# 2364_ROM-el_v2.net
KiCad netlist of a schematic drawn in EAGLE
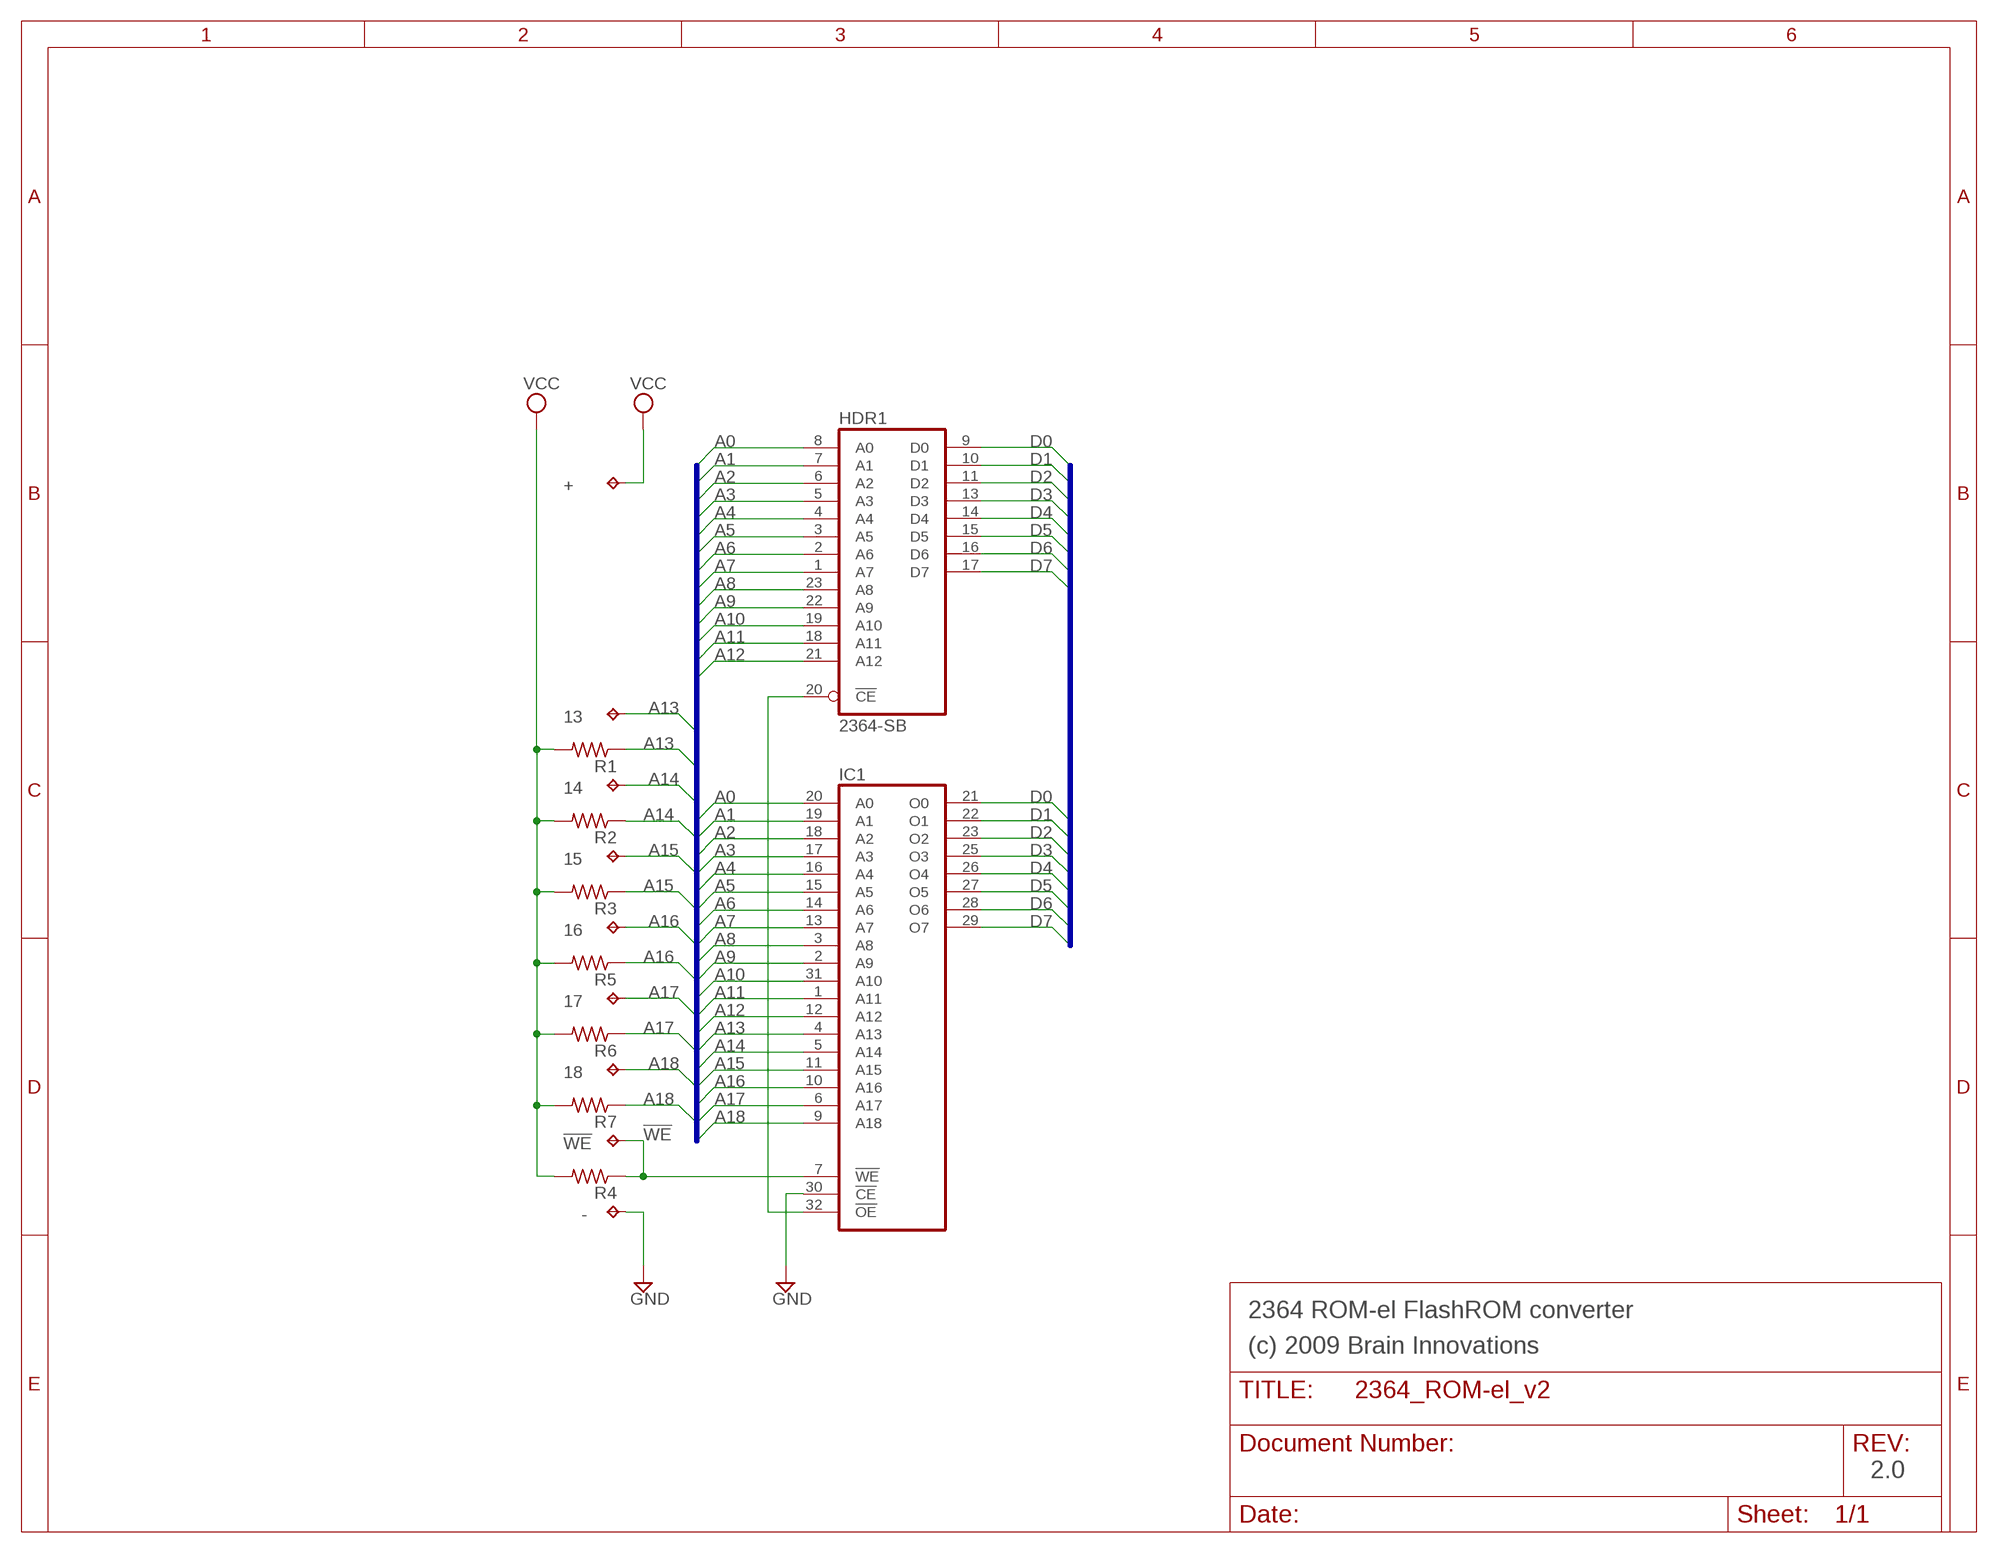
[diagram p0: schematic, sheet 1]

(export (version "E")
  (design (tool "Eeschema 10.0.6"))
  (components
    (comp (ref "!WE")
      (value "TPTP13SQ")
      (footprint "eagle-import:TP13SQ")
      (libsource (lib "eagle-import") (part "TPTP13SQ"))
    )
    (comp (ref "+")
      (value "TPTP13SQ")
      (footprint "eagle-import:TP13SQ")
      (libsource (lib "eagle-import") (part "TPTP13SQ"))
    )
    (comp (ref "-")
      (value "TPTP13SQ")
      (footprint "eagle-import:TP13SQ")
      (libsource (lib "eagle-import") (part "TPTP13SQ"))
    )
    (comp (ref "13")
      (value "TPTP13SQ")
      (footprint "eagle-import:TP13SQ")
      (libsource (lib "eagle-import") (part "TPTP13SQ"))
    )
    (comp (ref "14")
      (value "TPTP13SQ")
      (footprint "eagle-import:TP13SQ")
      (libsource (lib "eagle-import") (part "TPTP13SQ"))
    )
    (comp (ref "15")
      (value "TPTP13SQ")
      (footprint "eagle-import:TP13SQ")
      (libsource (lib "eagle-import") (part "TPTP13SQ"))
    )
    (comp (ref "16")
      (value "TPTP13SQ")
      (footprint "eagle-import:TP13SQ")
      (libsource (lib "eagle-import") (part "TPTP13SQ"))
    )
    (comp (ref "17")
      (value "TPTP13SQ")
      (footprint "eagle-import:TP13SQ")
      (libsource (lib "eagle-import") (part "TPTP13SQ"))
    )
    (comp (ref "18")
      (value "TPTP13SQ")
      (footprint "eagle-import:TP13SQ")
      (libsource (lib "eagle-import") (part "TPTP13SQ"))
    )
    (comp (ref "HDR1")
      (value "2364-SB")
      (footprint "eagle-import:DIL24-SMD-REVERSE")
      (libsource (lib "eagle-import") (part "2364-SB"))
    )
    (comp (ref "IC1")
      (value "FLASH_RAM4096KB'V'")
      (footprint "eagle-import:VSOP32")
      (libsource (lib "eagle-import") (part "FLASH_RAM4096KB'V'"))
    )
    (comp (ref "R1")
      (value "R-US_R0402")
      (footprint "eagle-import:R0402")
      (libsource (lib "eagle-import") (part "R-US_R0402"))
    )
    (comp (ref "R2")
      (value "R-US_R0402")
      (footprint "eagle-import:R0402")
      (libsource (lib "eagle-import") (part "R-US_R0402"))
    )
    (comp (ref "R3")
      (value "R-US_R0402")
      (footprint "eagle-import:R0402")
      (libsource (lib "eagle-import") (part "R-US_R0402"))
    )
    (comp (ref "R4")
      (value "R-US_R0402")
      (footprint "eagle-import:R0402")
      (libsource (lib "eagle-import") (part "R-US_R0402"))
    )
    (comp (ref "R5")
      (value "R-US_R0402")
      (footprint "eagle-import:R0402")
      (libsource (lib "eagle-import") (part "R-US_R0402"))
    )
    (comp (ref "R6")
      (value "R-US_R0402")
      (footprint "eagle-import:R0402")
      (libsource (lib "eagle-import") (part "R-US_R0402"))
    )
    (comp (ref "R7")
      (value "R-US_R0402")
      (footprint "eagle-import:R0402")
      (libsource (lib "eagle-import") (part "R-US_R0402"))
    )
  )
  (nets
    (net (code "1") (name "/A0") (class "Default")
      (node (ref "HDR1") (pin "8") (pinfunction "A0_8") (pintype "bidirectional"))
      (node (ref "IC1") (pin "20") (pinfunction "A0_20") (pintype "input"))
    )
    (net (code "2") (name "/A1") (class "Default")
      (node (ref "HDR1") (pin "7") (pinfunction "A1_7") (pintype "bidirectional"))
      (node (ref "IC1") (pin "19") (pinfunction "A1_19") (pintype "input"))
    )
    (net (code "3") (name "/A2") (class "Default")
      (node (ref "HDR1") (pin "6") (pinfunction "A2_6") (pintype "bidirectional"))
      (node (ref "IC1") (pin "18") (pinfunction "A2_18") (pintype "input"))
    )
    (net (code "4") (name "/A3") (class "Default")
      (node (ref "HDR1") (pin "5") (pinfunction "A3_5") (pintype "bidirectional"))
      (node (ref "IC1") (pin "17") (pinfunction "A3_17") (pintype "input"))
    )
    (net (code "5") (name "/A4") (class "Default")
      (node (ref "HDR1") (pin "4") (pinfunction "A4_4") (pintype "bidirectional"))
      (node (ref "IC1") (pin "16") (pinfunction "A4_16") (pintype "input"))
    )
    (net (code "6") (name "/A5") (class "Default")
      (node (ref "HDR1") (pin "3") (pinfunction "A5_3") (pintype "bidirectional"))
      (node (ref "IC1") (pin "15") (pinfunction "A5_15") (pintype "input"))
    )
    (net (code "7") (name "/A6") (class "Default")
      (node (ref "HDR1") (pin "2") (pinfunction "A6_2") (pintype "bidirectional"))
      (node (ref "IC1") (pin "14") (pinfunction "A6_14") (pintype "input"))
    )
    (net (code "8") (name "/A7") (class "Default")
      (node (ref "HDR1") (pin "1") (pinfunction "A7_1") (pintype "bidirectional"))
      (node (ref "IC1") (pin "13") (pinfunction "A7_13") (pintype "input"))
    )
    (net (code "9") (name "/A8") (class "Default")
      (node (ref "HDR1") (pin "23") (pinfunction "A8_23") (pintype "bidirectional"))
      (node (ref "IC1") (pin "3") (pinfunction "A8_3") (pintype "input"))
    )
    (net (code "10") (name "/A9") (class "Default")
      (node (ref "HDR1") (pin "22") (pinfunction "A9_22") (pintype "bidirectional"))
      (node (ref "IC1") (pin "2") (pinfunction "A9_2") (pintype "input"))
    )
    (net (code "11") (name "/A10") (class "Default")
      (node (ref "HDR1") (pin "19") (pinfunction "A10_19") (pintype "bidirectional"))
      (node (ref "IC1") (pin "31") (pinfunction "A10_31") (pintype "input"))
    )
    (net (code "12") (name "/A11") (class "Default")
      (node (ref "HDR1") (pin "18") (pinfunction "A11_18") (pintype "bidirectional"))
      (node (ref "IC1") (pin "1") (pinfunction "A11_1") (pintype "input"))
    )
    (net (code "13") (name "/A12") (class "Default")
      (node (ref "HDR1") (pin "21") (pinfunction "A12_21") (pintype "bidirectional"))
      (node (ref "IC1") (pin "12") (pinfunction "A12_12") (pintype "input"))
    )
    (net (code "14") (name "/A13") (class "Default")
      (node (ref "13") (pin "TP") (pinfunction "TP_TP") (pintype "input"))
      (node (ref "IC1") (pin "4") (pinfunction "A13_4") (pintype "input"))
      (node (ref "R1") (pin "1") (pinfunction "1_1") (pintype "passive"))
    )
    (net (code "15") (name "/A14") (class "Default")
      (node (ref "14") (pin "TP") (pinfunction "TP_TP") (pintype "input"))
      (node (ref "IC1") (pin "5") (pinfunction "A14_5") (pintype "input"))
      (node (ref "R2") (pin "1") (pinfunction "1_1") (pintype "passive"))
    )
    (net (code "16") (name "/A15") (class "Default")
      (node (ref "15") (pin "TP") (pinfunction "TP_TP") (pintype "input"))
      (node (ref "IC1") (pin "11") (pinfunction "A15_11") (pintype "input"))
      (node (ref "R3") (pin "1") (pinfunction "1_1") (pintype "passive"))
    )
    (net (code "17") (name "/A16") (class "Default")
      (node (ref "16") (pin "TP") (pinfunction "TP_TP") (pintype "input"))
      (node (ref "IC1") (pin "10") (pinfunction "A16_10") (pintype "input"))
      (node (ref "R5") (pin "1") (pinfunction "1_1") (pintype "passive"))
    )
    (net (code "18") (name "/A17") (class "Default")
      (node (ref "17") (pin "TP") (pinfunction "TP_TP") (pintype "input"))
      (node (ref "IC1") (pin "6") (pinfunction "A17_6") (pintype "input"))
      (node (ref "R6") (pin "1") (pinfunction "1_1") (pintype "passive"))
    )
    (net (code "19") (name "/A18") (class "Default")
      (node (ref "18") (pin "TP") (pinfunction "TP_TP") (pintype "input"))
      (node (ref "IC1") (pin "9") (pinfunction "A18_9") (pintype "input"))
      (node (ref "R7") (pin "1") (pinfunction "1_1") (pintype "passive"))
    )
    (net (code "20") (name "/D0") (class "Default")
      (node (ref "HDR1") (pin "9") (pinfunction "D0_9") (pintype "tri_state"))
      (node (ref "IC1") (pin "21") (pinfunction "O0_21") (pintype "tri_state"))
    )
    (net (code "21") (name "/D1") (class "Default")
      (node (ref "HDR1") (pin "10") (pinfunction "D1_10") (pintype "tri_state"))
      (node (ref "IC1") (pin "22") (pinfunction "O1_22") (pintype "tri_state"))
    )
    (net (code "22") (name "/D2") (class "Default")
      (node (ref "HDR1") (pin "11") (pinfunction "D2_11") (pintype "tri_state"))
      (node (ref "IC1") (pin "23") (pinfunction "O2_23") (pintype "tri_state"))
    )
    (net (code "23") (name "/D3") (class "Default")
      (node (ref "HDR1") (pin "13") (pinfunction "D3_13") (pintype "tri_state"))
      (node (ref "IC1") (pin "25") (pinfunction "O3_25") (pintype "tri_state"))
    )
    (net (code "24") (name "/D4") (class "Default")
      (node (ref "HDR1") (pin "14") (pinfunction "D4_14") (pintype "tri_state"))
      (node (ref "IC1") (pin "26") (pinfunction "O4_26") (pintype "tri_state"))
    )
    (net (code "25") (name "/D5") (class "Default")
      (node (ref "HDR1") (pin "15") (pinfunction "D5_15") (pintype "tri_state"))
      (node (ref "IC1") (pin "27") (pinfunction "O5_27") (pintype "tri_state"))
    )
    (net (code "26") (name "/D6") (class "Default")
      (node (ref "HDR1") (pin "16") (pinfunction "D6_16") (pintype "tri_state"))
      (node (ref "IC1") (pin "28") (pinfunction "O6_28") (pintype "tri_state"))
    )
    (net (code "27") (name "/D7") (class "Default")
      (node (ref "HDR1") (pin "17") (pinfunction "D7_17") (pintype "tri_state"))
      (node (ref "IC1") (pin "29") (pinfunction "O7_29") (pintype "tri_state"))
    )
    (net (code "28") (name "/~{WE}") (class "Default")
      (node (ref "!WE") (pin "TP") (pinfunction "TP_TP") (pintype "input"))
      (node (ref "IC1") (pin "7") (pinfunction "~{WE}_7") (pintype "input"))
      (node (ref "R4") (pin "1") (pinfunction "1_1") (pintype "passive"))
    )
    (net (code "29") (name "GND") (class "Default")
      (node (ref "-") (pin "TP") (pinfunction "TP_TP") (pintype "input"))
      (node (ref "IC1") (pin "30") (pinfunction "~{CE}_30") (pintype "input"))
    )
    (net (code "30") (name "Net-(HDR1A-~{CE})") (class "Default")
      (node (ref "HDR1") (pin "20") (pinfunction "~{CE}_20") (pintype "input"))
      (node (ref "IC1") (pin "32") (pinfunction "~{OE}_32") (pintype "input"))
    )
    (net (code "31") (name "VCC") (class "Default")
      (node (ref "+") (pin "TP") (pinfunction "TP_TP") (pintype "input"))
      (node (ref "R1") (pin "2") (pinfunction "2_2") (pintype "passive"))
      (node (ref "R2") (pin "2") (pinfunction "2_2") (pintype "passive"))
      (node (ref "R3") (pin "2") (pinfunction "2_2") (pintype "passive"))
      (node (ref "R4") (pin "2") (pinfunction "2_2") (pintype "passive"))
      (node (ref "R5") (pin "2") (pinfunction "2_2") (pintype "passive"))
      (node (ref "R6") (pin "2") (pinfunction "2_2") (pintype "passive"))
      (node (ref "R7") (pin "2") (pinfunction "2_2") (pintype "passive"))
    )
  )
)
